# XPDR_Board_2.net
KiCad netlist of a schematic drawn in EAGLE
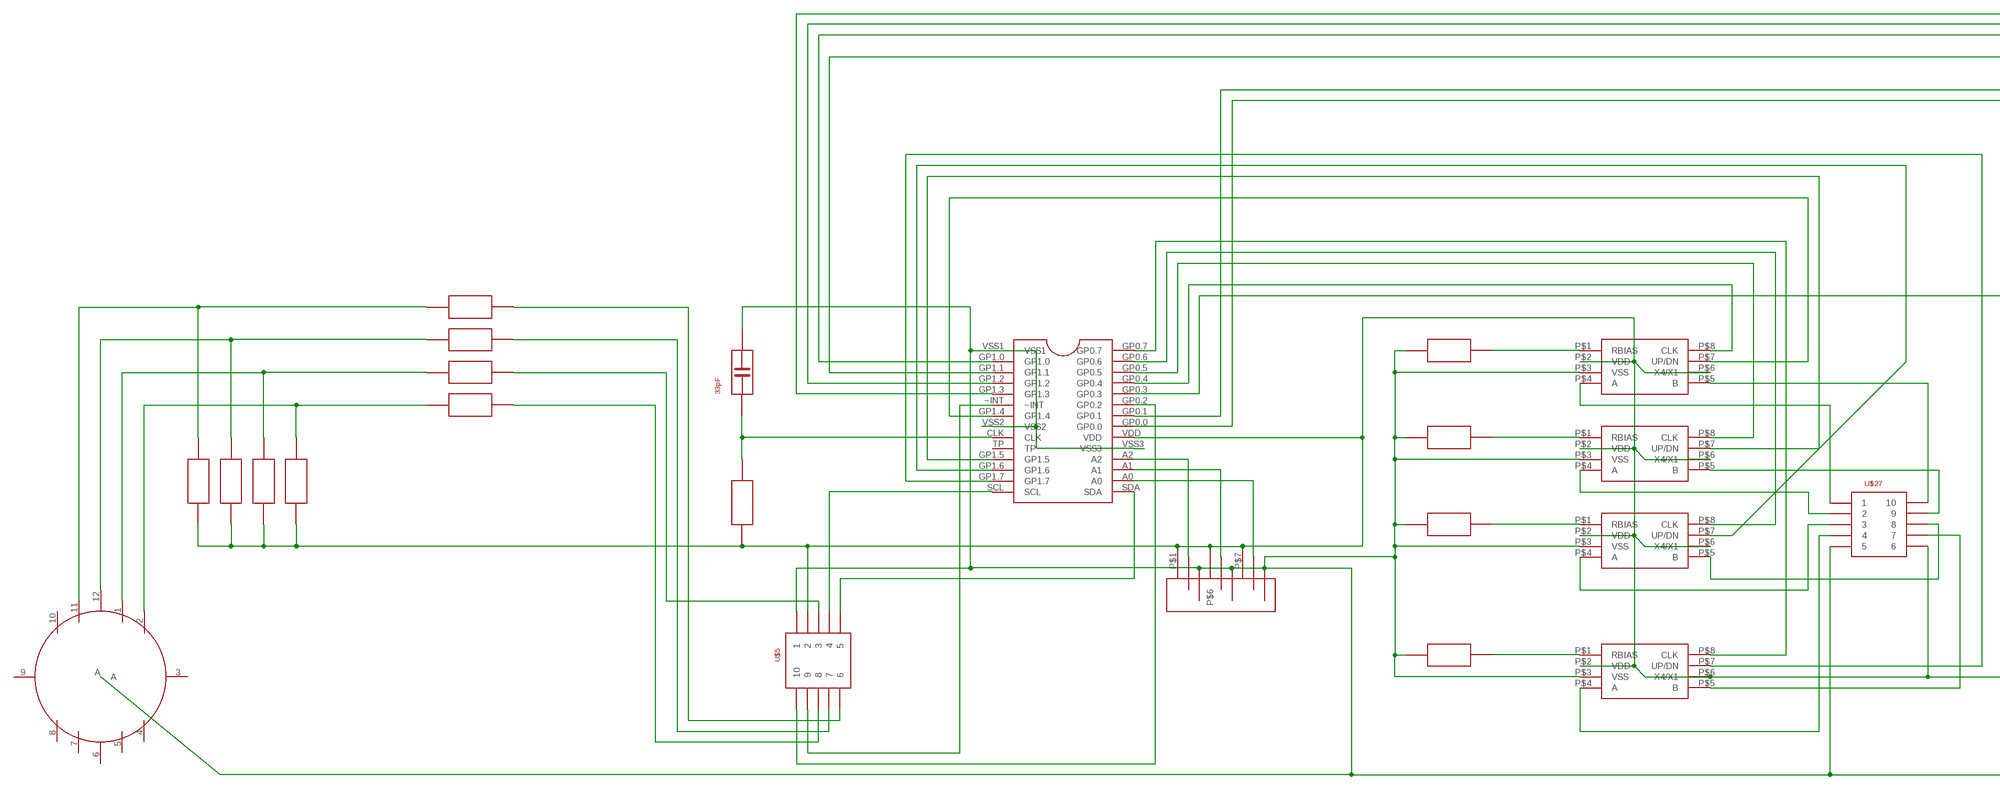
[diagram p0: schematic, sheet 1, part 1 of 2]
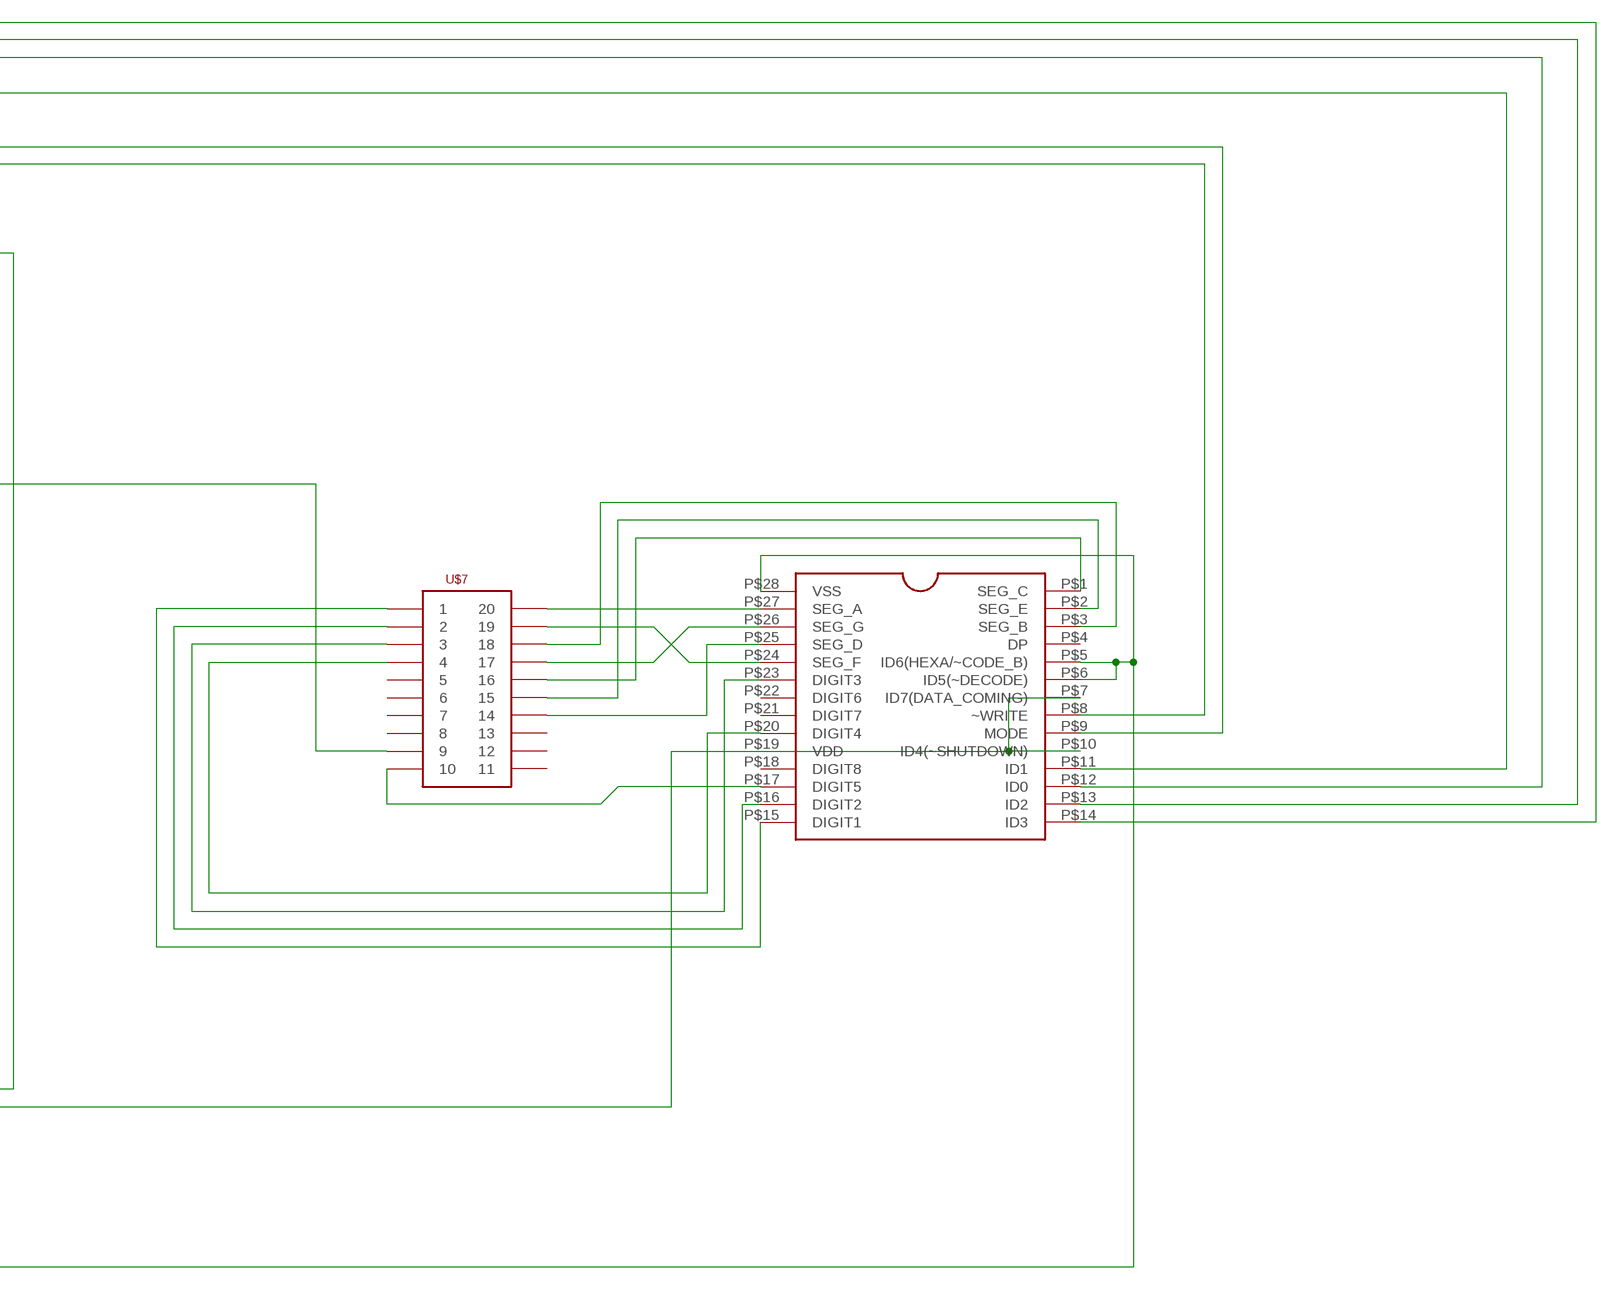
[diagram p1: schematic, sheet 1, part 2 of 2]

(export (version "E")
  (design (tool "Eeschema 10.0.6"))
  (components
    (comp (ref "U$1")
      (value "LS7084")
      (footprint "eagle-import:LS7084")
      (libsource (lib "eagle-import") (part "LS7084"))
    )
    (comp (ref "U$2")
      (value "LS7084")
      (footprint "eagle-import:LS7084")
      (libsource (lib "eagle-import") (part "LS7084"))
    )
    (comp (ref "U$3")
      (value "LS7084")
      (footprint "eagle-import:LS7084")
      (libsource (lib "eagle-import") (part "LS7084"))
    )
    (comp (ref "U$4")
      (value "LS7084")
      (footprint "eagle-import:LS7084")
      (libsource (lib "eagle-import") (part "LS7084"))
    )
    (comp (ref "U$5")
      (value "LISTA_2X5")
      (footprint "eagle-import:LISTA_2X5")
      (libsource (lib "eagle-import") (part "LISTA_2X5"))
    )
    (comp (ref "U$6")
      (value "ICM7228A")
      (footprint "eagle-import:ICM7228A")
      (libsource (lib "eagle-import") (part "ICM7228A"))
    )
    (comp (ref "U$7")
      (value "LISTA_2X10")
      (footprint "eagle-import:LISTA_2X10")
      (libsource (lib "eagle-import") (part "LISTA_2X10"))
    )
    (comp (ref "U$8")
      (value "470M")
      (footprint "eagle-import:REZISTOR")
      (libsource (lib "eagle-import") (part "REZISTOR"))
    )
    (comp (ref "U$9")
      (value "MCP23016")
      (footprint "eagle-import:MCP23016")
      (libsource (lib "eagle-import") (part "MCP23016"))
    )
    (comp (ref "U$10")
      (value "470M")
      (footprint "eagle-import:REZISTOR")
      (libsource (lib "eagle-import") (part "REZISTOR"))
    )
    (comp (ref "U$11")
      (value "ADRESA_0..2")
      (footprint "eagle-import:ADRESA_0..2")
      (libsource (lib "eagle-import") (part "ADRESA_0..2"))
    )
    (comp (ref "U$12")
      (value "470M")
      (footprint "eagle-import:REZISTOR")
      (libsource (lib "eagle-import") (part "REZISTOR"))
    )
    (comp (ref "U$13")
      (value "470M")
      (footprint "eagle-import:REZISTOR")
      (libsource (lib "eagle-import") (part "REZISTOR"))
    )
    (comp (ref "U$14")
      (value "3.9k")
      (footprint "eagle-import:REZISTOR")
      (libsource (lib "eagle-import") (part "REZISTOR"))
    )
    (comp (ref "U$15")
      (value "33pF")
      (footprint "eagle-import:KONDENZATOR")
      (libsource (lib "eagle-import") (part "KONDENZATOR"))
    )
    (comp (ref "U$16")
      (value "ROTARY_SWITCH")
      (footprint "eagle-import:ROTARY_SWITCH")
      (libsource (lib "eagle-import") (part "ROTARY_SWITCH"))
    )
    (comp (ref "U$17")
      (value "REZISTOR")
      (footprint "eagle-import:REZISTOR")
      (libsource (lib "eagle-import") (part "REZISTOR"))
    )
    (comp (ref "U$18")
      (value "REZISTOR")
      (footprint "eagle-import:REZISTOR")
      (libsource (lib "eagle-import") (part "REZISTOR"))
    )
    (comp (ref "U$19")
      (value "REZISTOR")
      (footprint "eagle-import:REZISTOR")
      (libsource (lib "eagle-import") (part "REZISTOR"))
    )
    (comp (ref "U$20")
      (value "REZISTOR")
      (footprint "eagle-import:REZISTOR")
      (libsource (lib "eagle-import") (part "REZISTOR"))
    )
    (comp (ref "U$21")
      (value "REZISTOR")
      (footprint "eagle-import:REZISTOR")
      (libsource (lib "eagle-import") (part "REZISTOR"))
    )
    (comp (ref "U$22")
      (value "REZISTOR")
      (footprint "eagle-import:REZISTOR")
      (libsource (lib "eagle-import") (part "REZISTOR"))
    )
    (comp (ref "U$23")
      (value "REZISTOR")
      (footprint "eagle-import:REZISTOR")
      (libsource (lib "eagle-import") (part "REZISTOR"))
    )
    (comp (ref "U$24")
      (value "REZISTOR")
      (footprint "eagle-import:REZISTOR")
      (libsource (lib "eagle-import") (part "REZISTOR"))
    )
    (comp (ref "U$27")
      (value "LISTA_2X5")
      (footprint "eagle-import:LISTA_2X5")
      (libsource (lib "eagle-import") (part "LISTA_2X5"))
    )
  )
  (nets
    (net (code "1") (name "Net-(U$1-A)") (class "Default")
      (node (ref "U$1") (pin "P$4") (pinfunction "A_P$4") (pintype "bidirectional"))
      (node (ref "U$27") (pin "1") (pinfunction "1_1") (pintype "bidirectional"))
    )
    (net (code "2") (name "Net-(U$1-B)") (class "Default")
      (node (ref "U$1") (pin "P$5") (pinfunction "B_P$5") (pintype "bidirectional"))
      (node (ref "U$27") (pin "10") (pinfunction "10_10") (pintype "bidirectional"))
    )
    (net (code "3") (name "Net-(U$1-CLK)") (class "Default")
      (node (ref "U$1") (pin "P$8") (pinfunction "CLK_P$8") (pintype "bidirectional"))
      (node (ref "U$9") (pin "GP0.4") (pinfunction "GP0.4_GP0.4") (pintype "bidirectional"))
    )
    (net (code "4") (name "Net-(U$1-RBIAS)") (class "Default")
      (node (ref "U$1") (pin "P$1") (pinfunction "RBIAS_P$1") (pintype "bidirectional"))
      (node (ref "U$8") (pin "P$2") (pinfunction "P$2_P$2") (pintype "bidirectional"))
    )
    (net (code "5") (name "Net-(U$1-UP{slash}DN)") (class "Default")
      (node (ref "U$1") (pin "P$7") (pinfunction "UP/DN_P$7") (pintype "bidirectional"))
      (node (ref "U$9") (pin "GP1.4") (pinfunction "GP1.4_GP1.4") (pintype "bidirectional"))
    )
    (net (code "6") (name "Net-(U$1-VDD)") (class "Default")
      (node (ref "U$1") (pin "P$2") (pinfunction "VDD_P$2") (pintype "bidirectional"))
      (node (ref "U$1") (pin "P$6") (pinfunction "X4/X1_P$6") (pintype "bidirectional"))
      (node (ref "U$11") (pin "P$1") (pinfunction "P$1_P$1") (pintype "bidirectional"))
      (node (ref "U$11") (pin "P$6") (pinfunction "P$6_P$6") (pintype "bidirectional"))
      (node (ref "U$11") (pin "P$7") (pinfunction "P$7_P$7") (pintype "bidirectional"))
      (node (ref "U$14") (pin "P$1") (pinfunction "P$1_P$1") (pintype "bidirectional"))
      (node (ref "U$17") (pin "P$1") (pinfunction "P$1_P$1") (pintype "bidirectional"))
      (node (ref "U$18") (pin "P$1") (pinfunction "P$1_P$1") (pintype "bidirectional"))
      (node (ref "U$19") (pin "P$1") (pinfunction "P$1_P$1") (pintype "bidirectional"))
      (node (ref "U$2") (pin "P$2") (pinfunction "VDD_P$2") (pintype "bidirectional"))
      (node (ref "U$2") (pin "P$6") (pinfunction "X4/X1_P$6") (pintype "bidirectional"))
      (node (ref "U$20") (pin "P$1") (pinfunction "P$1_P$1") (pintype "bidirectional"))
      (node (ref "U$27") (pin "6") (pinfunction "6_6") (pintype "bidirectional"))
      (node (ref "U$3") (pin "P$2") (pinfunction "VDD_P$2") (pintype "bidirectional"))
      (node (ref "U$3") (pin "P$6") (pinfunction "X4/X1_P$6") (pintype "bidirectional"))
      (node (ref "U$4") (pin "P$2") (pinfunction "VDD_P$2") (pintype "bidirectional"))
      (node (ref "U$4") (pin "P$6") (pinfunction "X4/X1_P$6") (pintype "bidirectional"))
      (node (ref "U$5") (pin "2") (pinfunction "2_2") (pintype "bidirectional"))
      (node (ref "U$6") (pin "P$10") (pinfunction "ID4(~{SHUTDOWN})_P$10") (pintype "bidirectional"))
      (node (ref "U$6") (pin "P$19") (pinfunction "VDD_P$19") (pintype "bidirectional"))
      (node (ref "U$6") (pin "P$7") (pinfunction "ID7(DATA_COMING)_P$7") (pintype "bidirectional"))
      (node (ref "U$9") (pin "VDD") (pinfunction "VDD_VDD") (pintype "bidirectional"))
    )
    (net (code "7") (name "Net-(U$1-VSS)") (class "Default")
      (node (ref "U$1") (pin "P$3") (pinfunction "VSS_P$3") (pintype "bidirectional"))
      (node (ref "U$10") (pin "P$1") (pinfunction "P$1_P$1") (pintype "bidirectional"))
      (node (ref "U$11") (pin "P$3") (pinfunction "P$3_P$3") (pintype "bidirectional"))
      (node (ref "U$11") (pin "P$4") (pinfunction "P$4_P$4") (pintype "bidirectional"))
      (node (ref "U$11") (pin "P$9") (pinfunction "P$9_P$9") (pintype "bidirectional"))
      (node (ref "U$12") (pin "P$1") (pinfunction "P$1_P$1") (pintype "bidirectional"))
      (node (ref "U$13") (pin "P$1") (pinfunction "P$1_P$1") (pintype "bidirectional"))
      (node (ref "U$15") (pin "P$2") (pinfunction "P$2_P$2") (pintype "bidirectional"))
      (node (ref "U$16") (pin "A") (pinfunction "A_A") (pintype "bidirectional"))
      (node (ref "U$2") (pin "P$3") (pinfunction "VSS_P$3") (pintype "bidirectional"))
      (node (ref "U$27") (pin "5") (pinfunction "5_5") (pintype "bidirectional"))
      (node (ref "U$3") (pin "P$3") (pinfunction "VSS_P$3") (pintype "bidirectional"))
      (node (ref "U$4") (pin "P$3") (pinfunction "VSS_P$3") (pintype "bidirectional"))
      (node (ref "U$5") (pin "1") (pinfunction "1_1") (pintype "bidirectional"))
      (node (ref "U$6") (pin "P$28") (pinfunction "VSS_P$28") (pintype "bidirectional"))
      (node (ref "U$6") (pin "P$5") (pinfunction "ID6(HEXA/~{CODE_B})_P$5") (pintype "bidirectional"))
      (node (ref "U$6") (pin "P$6") (pinfunction "ID5(~{DECODE})_P$6") (pintype "bidirectional"))
      (node (ref "U$8") (pin "P$1") (pinfunction "P$1_P$1") (pintype "bidirectional"))
      (node (ref "U$9") (pin "VSS1") (pinfunction "VSS1_VSS1") (pintype "bidirectional"))
      (node (ref "U$9") (pin "VSS2") (pinfunction "VSS2_VSS2") (pintype "bidirectional"))
      (node (ref "U$9") (pin "VSS3") (pinfunction "VSS3_VSS3") (pintype "bidirectional"))
    )
    (net (code "8") (name "Net-(U$2-A)") (class "Default")
      (node (ref "U$2") (pin "P$4") (pinfunction "A_P$4") (pintype "bidirectional"))
      (node (ref "U$27") (pin "2") (pinfunction "2_2") (pintype "bidirectional"))
    )
    (net (code "9") (name "Net-(U$2-B)") (class "Default")
      (node (ref "U$2") (pin "P$5") (pinfunction "B_P$5") (pintype "bidirectional"))
      (node (ref "U$27") (pin "9") (pinfunction "9_9") (pintype "bidirectional"))
    )
    (net (code "10") (name "Net-(U$2-CLK)") (class "Default")
      (node (ref "U$2") (pin "P$8") (pinfunction "CLK_P$8") (pintype "bidirectional"))
      (node (ref "U$9") (pin "GP0.5") (pinfunction "GP0.5_GP0.5") (pintype "bidirectional"))
    )
    (net (code "11") (name "Net-(U$2-RBIAS)") (class "Default")
      (node (ref "U$10") (pin "P$2") (pinfunction "P$2_P$2") (pintype "bidirectional"))
      (node (ref "U$2") (pin "P$1") (pinfunction "RBIAS_P$1") (pintype "bidirectional"))
    )
    (net (code "12") (name "Net-(U$2-UP{slash}DN)") (class "Default")
      (node (ref "U$2") (pin "P$7") (pinfunction "UP/DN_P$7") (pintype "bidirectional"))
      (node (ref "U$9") (pin "GP1.5") (pinfunction "GP1.5_GP1.5") (pintype "bidirectional"))
    )
    (net (code "13") (name "Net-(U$3-A)") (class "Default")
      (node (ref "U$27") (pin "3") (pinfunction "3_3") (pintype "bidirectional"))
      (node (ref "U$3") (pin "P$4") (pinfunction "A_P$4") (pintype "bidirectional"))
    )
    (net (code "14") (name "Net-(U$3-B)") (class "Default")
      (node (ref "U$27") (pin "8") (pinfunction "8_8") (pintype "bidirectional"))
      (node (ref "U$3") (pin "P$5") (pinfunction "B_P$5") (pintype "bidirectional"))
    )
    (net (code "15") (name "Net-(U$3-CLK)") (class "Default")
      (node (ref "U$3") (pin "P$8") (pinfunction "CLK_P$8") (pintype "bidirectional"))
      (node (ref "U$9") (pin "GP0.6") (pinfunction "GP0.6_GP0.6") (pintype "bidirectional"))
    )
    (net (code "16") (name "Net-(U$3-RBIAS)") (class "Default")
      (node (ref "U$12") (pin "P$2") (pinfunction "P$2_P$2") (pintype "bidirectional"))
      (node (ref "U$3") (pin "P$1") (pinfunction "RBIAS_P$1") (pintype "bidirectional"))
    )
    (net (code "17") (name "Net-(U$3-UP{slash}DN)") (class "Default")
      (node (ref "U$3") (pin "P$7") (pinfunction "UP/DN_P$7") (pintype "bidirectional"))
      (node (ref "U$9") (pin "GP1.6") (pinfunction "GP1.6_GP1.6") (pintype "bidirectional"))
    )
    (net (code "18") (name "Net-(U$4-A)") (class "Default")
      (node (ref "U$27") (pin "4") (pinfunction "4_4") (pintype "bidirectional"))
      (node (ref "U$4") (pin "P$4") (pinfunction "A_P$4") (pintype "bidirectional"))
    )
    (net (code "19") (name "Net-(U$4-B)") (class "Default")
      (node (ref "U$27") (pin "7") (pinfunction "7_7") (pintype "bidirectional"))
      (node (ref "U$4") (pin "P$5") (pinfunction "B_P$5") (pintype "bidirectional"))
    )
    (net (code "20") (name "Net-(U$4-CLK)") (class "Default")
      (node (ref "U$4") (pin "P$8") (pinfunction "CLK_P$8") (pintype "bidirectional"))
      (node (ref "U$9") (pin "GP0.7") (pinfunction "GP0.7_GP0.7") (pintype "bidirectional"))
    )
    (net (code "21") (name "Net-(U$4-RBIAS)") (class "Default")
      (node (ref "U$13") (pin "P$2") (pinfunction "P$2_P$2") (pintype "bidirectional"))
      (node (ref "U$4") (pin "P$1") (pinfunction "RBIAS_P$1") (pintype "bidirectional"))
    )
    (net (code "22") (name "Net-(U$4-UP{slash}DN)") (class "Default")
      (node (ref "U$4") (pin "P$7") (pinfunction "UP/DN_P$7") (pintype "bidirectional"))
      (node (ref "U$9") (pin "GP1.7") (pinfunction "GP1.7_GP1.7") (pintype "bidirectional"))
    )
    (net (code "23") (name "Net-(U$5-Pad4)") (class "Default")
      (node (ref "U$5") (pin "4") (pinfunction "4_4") (pintype "bidirectional"))
      (node (ref "U$9") (pin "SCL") (pinfunction "SCL_SCL") (pintype "bidirectional"))
    )
    (net (code "24") (name "Net-(U$5-Pad5)") (class "Default")
      (node (ref "U$5") (pin "5") (pinfunction "5_5") (pintype "bidirectional"))
      (node (ref "U$9") (pin "SDA") (pinfunction "SDA_SDA") (pintype "bidirectional"))
    )
    (net (code "25") (name "Net-(U$5-Pad10)") (class "Default")
      (node (ref "U$5") (pin "10") (pinfunction "10_10") (pintype "bidirectional"))
      (node (ref "U$9") (pin "GP0.2") (pinfunction "GP0.2_GP0.2") (pintype "bidirectional"))
    )
    (net (code "26") (name "Net-(U$6-DIGIT1)") (class "Default")
      (node (ref "U$6") (pin "P$15") (pinfunction "DIGIT1_P$15") (pintype "bidirectional"))
      (node (ref "U$7") (pin "1") (pinfunction "1_1") (pintype "bidirectional"))
    )
    (net (code "27") (name "Net-(U$6-DIGIT2)") (class "Default")
      (node (ref "U$6") (pin "P$16") (pinfunction "DIGIT2_P$16") (pintype "bidirectional"))
      (node (ref "U$7") (pin "2") (pinfunction "2_2") (pintype "bidirectional"))
    )
    (net (code "28") (name "Net-(U$6-DIGIT3)") (class "Default")
      (node (ref "U$6") (pin "P$23") (pinfunction "DIGIT3_P$23") (pintype "bidirectional"))
      (node (ref "U$7") (pin "3") (pinfunction "3_3") (pintype "bidirectional"))
    )
    (net (code "29") (name "Net-(U$6-DIGIT4)") (class "Default")
      (node (ref "U$6") (pin "P$20") (pinfunction "DIGIT4_P$20") (pintype "bidirectional"))
      (node (ref "U$7") (pin "4") (pinfunction "4_4") (pintype "bidirectional"))
    )
    (net (code "30") (name "Net-(U$6-DIGIT5)") (class "Default")
      (node (ref "U$6") (pin "P$17") (pinfunction "DIGIT5_P$17") (pintype "bidirectional"))
      (node (ref "U$7") (pin "10") (pinfunction "10_10") (pintype "bidirectional"))
    )
    (net (code "31") (name "Net-(U$6-ID0)") (class "Default")
      (node (ref "U$6") (pin "P$12") (pinfunction "ID0_P$12") (pintype "bidirectional"))
      (node (ref "U$9") (pin "GP1.0") (pinfunction "GP1.0_GP1.0") (pintype "bidirectional"))
    )
    (net (code "32") (name "Net-(U$6-ID1)") (class "Default")
      (node (ref "U$6") (pin "P$11") (pinfunction "ID1_P$11") (pintype "bidirectional"))
      (node (ref "U$9") (pin "GP1.1") (pinfunction "GP1.1_GP1.1") (pintype "bidirectional"))
    )
    (net (code "33") (name "Net-(U$6-ID2)") (class "Default")
      (node (ref "U$6") (pin "P$13") (pinfunction "ID2_P$13") (pintype "bidirectional"))
      (node (ref "U$9") (pin "GP1.2") (pinfunction "GP1.2_GP1.2") (pintype "bidirectional"))
    )
    (net (code "34") (name "Net-(U$6-ID3)") (class "Default")
      (node (ref "U$6") (pin "P$14") (pinfunction "ID3_P$14") (pintype "bidirectional"))
      (node (ref "U$9") (pin "GP1.3") (pinfunction "GP1.3_GP1.3") (pintype "bidirectional"))
    )
    (net (code "35") (name "Net-(U$6-MODE)") (class "Default")
      (node (ref "U$6") (pin "P$9") (pinfunction "MODE_P$9") (pintype "bidirectional"))
      (node (ref "U$9") (pin "GP0.1") (pinfunction "GP0.1_GP0.1") (pintype "bidirectional"))
    )
    (net (code "36") (name "Net-(U$6-SEG_A)") (class "Default")
      (node (ref "U$6") (pin "P$27") (pinfunction "SEG_A_P$27") (pintype "bidirectional"))
      (node (ref "U$7") (pin "20") (pinfunction "20_20") (pintype "bidirectional"))
    )
    (net (code "37") (name "Net-(U$6-SEG_B)") (class "Default")
      (node (ref "U$6") (pin "P$3") (pinfunction "SEG_B_P$3") (pintype "bidirectional"))
      (node (ref "U$7") (pin "18") (pinfunction "18_18") (pintype "bidirectional"))
    )
    (net (code "38") (name "Net-(U$6-SEG_C)") (class "Default")
      (node (ref "U$6") (pin "P$1") (pinfunction "SEG_C_P$1") (pintype "bidirectional"))
      (node (ref "U$7") (pin "16") (pinfunction "16_16") (pintype "bidirectional"))
    )
    (net (code "39") (name "Net-(U$6-SEG_D)") (class "Default")
      (node (ref "U$6") (pin "P$25") (pinfunction "SEG_D_P$25") (pintype "bidirectional"))
      (node (ref "U$7") (pin "14") (pinfunction "14_14") (pintype "bidirectional"))
    )
    (net (code "40") (name "Net-(U$6-SEG_E)") (class "Default")
      (node (ref "U$6") (pin "P$2") (pinfunction "SEG_E_P$2") (pintype "bidirectional"))
      (node (ref "U$7") (pin "15") (pinfunction "15_15") (pintype "bidirectional"))
    )
    (net (code "41") (name "Net-(U$6-SEG_F)") (class "Default")
      (node (ref "U$6") (pin "P$24") (pinfunction "SEG_F_P$24") (pintype "bidirectional"))
      (node (ref "U$7") (pin "19") (pinfunction "19_19") (pintype "bidirectional"))
    )
    (net (code "42") (name "Net-(U$6-SEG_G)") (class "Default")
      (node (ref "U$6") (pin "P$26") (pinfunction "SEG_G_P$26") (pintype "bidirectional"))
      (node (ref "U$7") (pin "17") (pinfunction "17_17") (pintype "bidirectional"))
    )
    (net (code "43") (name "Net-(U$6-~{WRITE})") (class "Default")
      (node (ref "U$6") (pin "P$8") (pinfunction "~{WRITE}_P$8") (pintype "bidirectional"))
      (node (ref "U$9") (pin "GP0.0") (pinfunction "GP0.0_GP0.0") (pintype "bidirectional"))
    )
    (net (code "44") (name "Net-(U$7-Pad9)") (class "Default")
      (node (ref "U$7") (pin "9") (pinfunction "9_9") (pintype "bidirectional"))
      (node (ref "U$9") (pin "GP0.3") (pinfunction "GP0.3_GP0.3") (pintype "bidirectional"))
    )
    (net (code "45") (name "Net-(U$9-~{INT})") (class "Default")
      (node (ref "U$5") (pin "9") (pinfunction "9_9") (pintype "bidirectional"))
      (node (ref "U$9") (pin "~INT") (pinfunction "~{INT}_~INT") (pintype "bidirectional"))
    )
    (net (code "46") (name "Net-(U$11-PadP$2)") (class "Default")
      (node (ref "U$11") (pin "P$2") (pinfunction "P$2_P$2") (pintype "bidirectional"))
      (node (ref "U$9") (pin "A2") (pinfunction "A2_A2") (pintype "bidirectional"))
    )
    (net (code "47") (name "Net-(U$11-PadP$5)") (class "Default")
      (node (ref "U$11") (pin "P$5") (pinfunction "P$5_P$5") (pintype "bidirectional"))
      (node (ref "U$9") (pin "A1") (pinfunction "A1_A1") (pintype "bidirectional"))
    )
    (net (code "48") (name "Net-(U$11-PadP$8)") (class "Default")
      (node (ref "U$11") (pin "P$8") (pinfunction "P$8_P$8") (pintype "bidirectional"))
      (node (ref "U$9") (pin "A0") (pinfunction "A0_A0") (pintype "bidirectional"))
    )
    (net (code "49") (name "Net-(U$14-PadP$2)") (class "Default")
      (node (ref "U$14") (pin "P$2") (pinfunction "P$2_P$2") (pintype "bidirectional"))
      (node (ref "U$15") (pin "P$1") (pinfunction "P$1_P$1") (pintype "bidirectional"))
      (node (ref "U$9") (pin "CLK") (pinfunction "CLK_CLK") (pintype "bidirectional"))
    )
    (net (code "50") (name "Net-(U$16-Pad1)") (class "Default")
      (node (ref "U$16") (pin "1") (pinfunction "1_1") (pintype "bidirectional"))
      (node (ref "U$19") (pin "P$2") (pinfunction "P$2_P$2") (pintype "bidirectional"))
      (node (ref "U$23") (pin "P$2") (pinfunction "P$2_P$2") (pintype "bidirectional"))
    )
    (net (code "51") (name "Net-(U$16-Pad2)") (class "Default")
      (node (ref "U$16") (pin "2") (pinfunction "2_2") (pintype "bidirectional"))
      (node (ref "U$20") (pin "P$2") (pinfunction "P$2_P$2") (pintype "bidirectional"))
      (node (ref "U$24") (pin "P$2") (pinfunction "P$2_P$2") (pintype "bidirectional"))
    )
    (net (code "52") (name "Net-(U$16-Pad11)") (class "Default")
      (node (ref "U$16") (pin "11") (pinfunction "11_11") (pintype "bidirectional"))
      (node (ref "U$17") (pin "P$2") (pinfunction "P$2_P$2") (pintype "bidirectional"))
      (node (ref "U$21") (pin "P$2") (pinfunction "P$2_P$2") (pintype "bidirectional"))
    )
    (net (code "53") (name "Net-(U$16-Pad12)") (class "Default")
      (node (ref "U$16") (pin "12") (pinfunction "12_12") (pintype "bidirectional"))
      (node (ref "U$18") (pin "P$2") (pinfunction "P$2_P$2") (pintype "bidirectional"))
      (node (ref "U$22") (pin "P$2") (pinfunction "P$2_P$2") (pintype "bidirectional"))
    )
    (net (code "54") (name "Net-(U$21-PadP$1)") (class "Default")
      (node (ref "U$21") (pin "P$1") (pinfunction "P$1_P$1") (pintype "bidirectional"))
      (node (ref "U$5") (pin "6") (pinfunction "6_6") (pintype "bidirectional"))
    )
    (net (code "55") (name "Net-(U$22-PadP$1)") (class "Default")
      (node (ref "U$22") (pin "P$1") (pinfunction "P$1_P$1") (pintype "bidirectional"))
      (node (ref "U$5") (pin "7") (pinfunction "7_7") (pintype "bidirectional"))
    )
    (net (code "56") (name "Net-(U$23-PadP$1)") (class "Default")
      (node (ref "U$23") (pin "P$1") (pinfunction "P$1_P$1") (pintype "bidirectional"))
      (node (ref "U$5") (pin "3") (pinfunction "3_3") (pintype "bidirectional"))
    )
    (net (code "57") (name "Net-(U$24-PadP$1)") (class "Default")
      (node (ref "U$24") (pin "P$1") (pinfunction "P$1_P$1") (pintype "bidirectional"))
      (node (ref "U$5") (pin "8") (pinfunction "8_8") (pintype "bidirectional"))
    )
    (net (code "58") (name "unconnected-(U$6-DIGIT6-PadP$22)") (class "Default")
      (node (ref "U$6") (pin "P$22") (pinfunction "DIGIT6_P$22") (pintype "bidirectional"))
    )
    (net (code "59") (name "unconnected-(U$6-DIGIT7-PadP$21)") (class "Default")
      (node (ref "U$6") (pin "P$21") (pinfunction "DIGIT7_P$21") (pintype "bidirectional"))
    )
    (net (code "60") (name "unconnected-(U$6-DIGIT8-PadP$18)") (class "Default")
      (node (ref "U$6") (pin "P$18") (pinfunction "DIGIT8_P$18") (pintype "bidirectional"))
    )
    (net (code "61") (name "unconnected-(U$6-DP-PadP$4)") (class "Default")
      (node (ref "U$6") (pin "P$4") (pinfunction "DP_P$4") (pintype "bidirectional"))
    )
    (net (code "62") (name "unconnected-(U$7-Pad5)") (class "Default")
      (node (ref "U$7") (pin "5") (pinfunction "5_5") (pintype "bidirectional"))
    )
    (net (code "63") (name "unconnected-(U$7-Pad6)") (class "Default")
      (node (ref "U$7") (pin "6") (pinfunction "6_6") (pintype "bidirectional"))
    )
    (net (code "64") (name "unconnected-(U$7-Pad7)") (class "Default")
      (node (ref "U$7") (pin "7") (pinfunction "7_7") (pintype "bidirectional"))
    )
    (net (code "65") (name "unconnected-(U$7-Pad8)") (class "Default")
      (node (ref "U$7") (pin "8") (pinfunction "8_8") (pintype "bidirectional"))
    )
    (net (code "66") (name "unconnected-(U$7-Pad11)") (class "Default")
      (node (ref "U$7") (pin "11") (pinfunction "11_11") (pintype "bidirectional"))
    )
    (net (code "67") (name "unconnected-(U$7-Pad12)") (class "Default")
      (node (ref "U$7") (pin "12") (pinfunction "12_12") (pintype "bidirectional"))
    )
    (net (code "68") (name "unconnected-(U$7-Pad13)") (class "Default")
      (node (ref "U$7") (pin "13") (pinfunction "13_13") (pintype "bidirectional"))
    )
    (net (code "69") (name "unconnected-(U$9-PadTP)") (class "Default")
      (node (ref "U$9") (pin "TP") (pinfunction "TP_TP") (pintype "bidirectional"))
    )
    (net (code "70") (name "unconnected-(U$16-Pad3)") (class "Default")
      (node (ref "U$16") (pin "3") (pinfunction "3_3") (pintype "bidirectional"))
    )
    (net (code "71") (name "unconnected-(U$16-Pad4)") (class "Default")
      (node (ref "U$16") (pin "4") (pinfunction "4_4") (pintype "bidirectional"))
    )
    (net (code "72") (name "unconnected-(U$16-Pad5)") (class "Default")
      (node (ref "U$16") (pin "5") (pinfunction "5_5") (pintype "bidirectional"))
    )
    (net (code "73") (name "unconnected-(U$16-Pad6)") (class "Default")
      (node (ref "U$16") (pin "6") (pinfunction "6_6") (pintype "bidirectional"))
    )
    (net (code "74") (name "unconnected-(U$16-Pad7)") (class "Default")
      (node (ref "U$16") (pin "7") (pinfunction "7_7") (pintype "bidirectional"))
    )
    (net (code "75") (name "unconnected-(U$16-Pad8)") (class "Default")
      (node (ref "U$16") (pin "8") (pinfunction "8_8") (pintype "bidirectional"))
    )
    (net (code "76") (name "unconnected-(U$16-Pad9)") (class "Default")
      (node (ref "U$16") (pin "9") (pinfunction "9_9") (pintype "bidirectional"))
    )
    (net (code "77") (name "unconnected-(U$16-Pad10)") (class "Default")
      (node (ref "U$16") (pin "10") (pinfunction "10_10") (pintype "bidirectional"))
    )
  )
)
